# Duckuino1.net
KiCad netlist of a schematic drawn in EAGLE
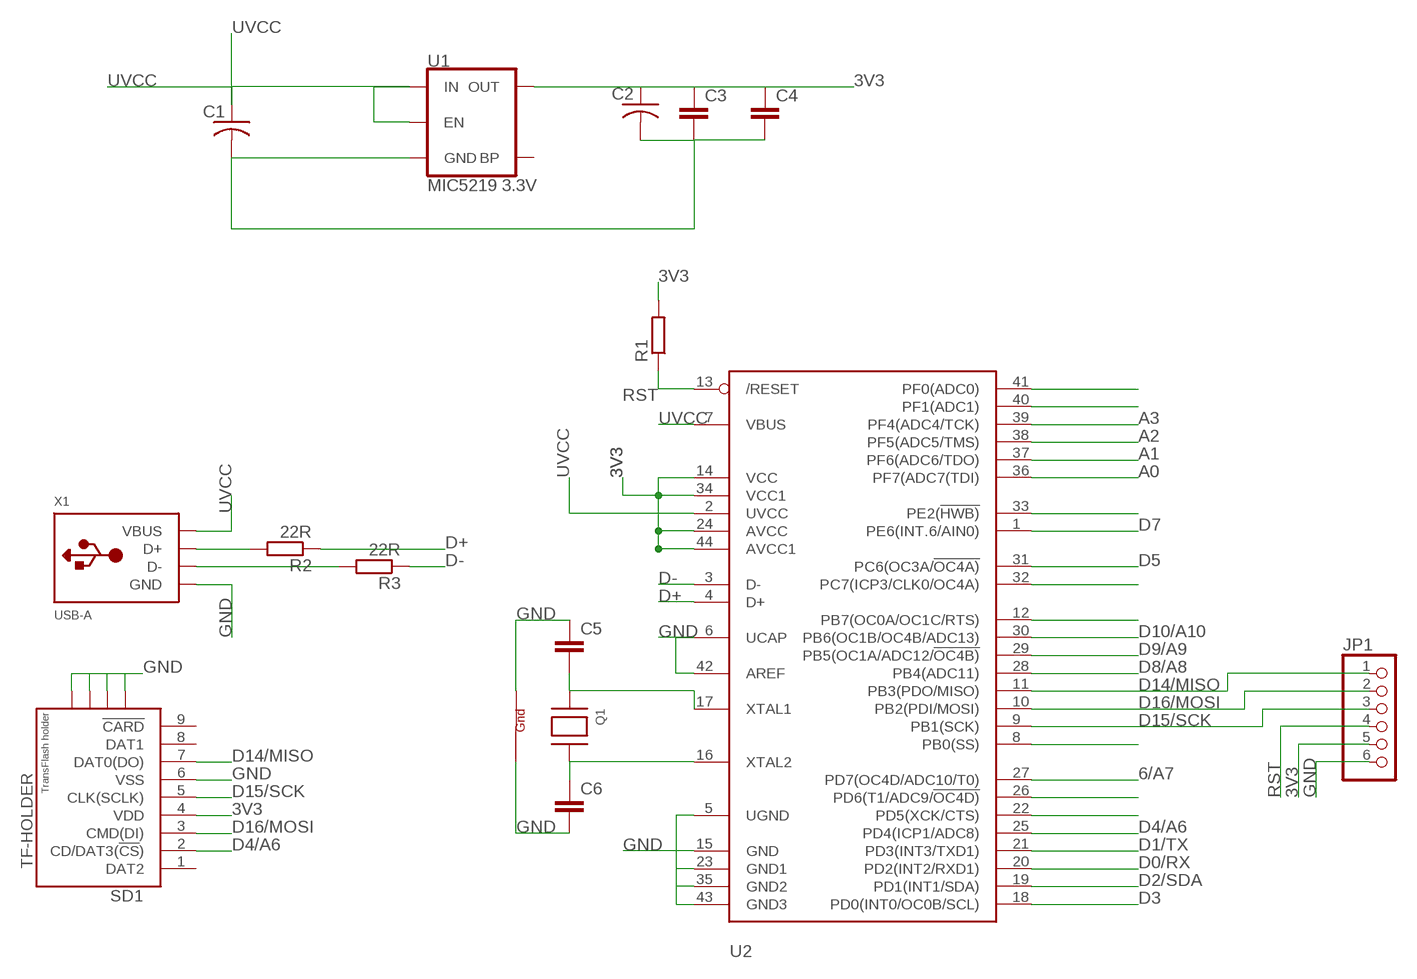
[diagram p0: schematic, sheet 1]

(export (version "E")
  (design (tool "Eeschema 10.0.6"))
  (components
    (comp (ref "C1")
      (value "C-USC0603")
      (footprint "eagle-import:C0603")
      (libsource (lib "eagle-import") (part "C-USC0603"))
    )
    (comp (ref "C2")
      (value "C-USC0603")
      (footprint "eagle-import:C0603")
      (libsource (lib "eagle-import") (part "C-USC0603"))
    )
    (comp (ref "C3")
      (value "C-EUC0603")
      (footprint "eagle-import:C0603")
      (libsource (lib "eagle-import") (part "C-EUC0603"))
    )
    (comp (ref "C4")
      (value "C-EUC0603")
      (footprint "eagle-import:C0603")
      (libsource (lib "eagle-import") (part "C-EUC0603"))
    )
    (comp (ref "C5")
      (value "C-EUC0603")
      (footprint "eagle-import:C0603")
      (libsource (lib "eagle-import") (part "C-EUC0603"))
    )
    (comp (ref "C6")
      (value "C-EUC0603")
      (footprint "eagle-import:C0603")
      (libsource (lib "eagle-import") (part "C-EUC0603"))
    )
    (comp (ref "JP1")
      (value "PINHD-1X6")
      (footprint "eagle-import:1X06")
      (libsource (lib "eagle-import") (part "PINHD-1X6"))
    )
    (comp (ref "Q1")
      (value "XTAL-4-3225")
      (footprint "eagle-import:NX3225")
      (libsource (lib "eagle-import") (part "XTAL-4-3225"))
    )
    (comp (ref "R1")
      (value "RR0603")
      (footprint "eagle-import:R0603")
      (libsource (lib "eagle-import") (part "RR0603"))
    )
    (comp (ref "R2")
      (value "22R")
      (footprint "eagle-import:R0603")
      (libsource (lib "eagle-import") (part "RR0603"))
    )
    (comp (ref "R3")
      (value "22R")
      (footprint "eagle-import:R0603")
      (libsource (lib "eagle-import") (part "RR0603"))
    )
    (comp (ref "SD1")
      (value "TF-HOLDER")
      (footprint "eagle-import:TF-PULL")
      (libsource (lib "eagle-import") (part "TF-HOLDER"))
    )
    (comp (ref "U1")
      (value "MIC5219 3.3V")
      (footprint "eagle-import:SOT23-5")
      (libsource (lib "eagle-import") (part "V_REG_MIC52193.3V"))
    )
    (comp (ref "U2")
      (value "ATMEGA32U4-AU")
      (footprint "eagle-import:TQFP44")
      (libsource (lib "eagle-import") (part "ATMEGA32U4-AU"))
    )
    (comp (ref "X1")
      (value "USB-A")
      (footprint "eagle-import:MOLEX_480371000")
      (libsource (lib "eagle-import") (part "USB-A"))
    )
  )
  (nets
    (net (code "1") (name "/3V3") (class "Default")
      (node (ref "C2") (pin "1") (pinfunction "1_1") (pintype "passive"))
      (node (ref "C3") (pin "1") (pinfunction "1_1") (pintype "passive"))
      (node (ref "C4") (pin "1") (pinfunction "1_1") (pintype "passive"))
      (node (ref "JP1") (pin "5") (pinfunction "5_5") (pintype "passive"))
      (node (ref "R1") (pin "2") (pinfunction "2_2") (pintype "passive"))
      (node (ref "SD1") (pin "4") (pinfunction "VDD_4") (pintype "power_in"))
      (node (ref "U1") (pin "5") (pinfunction "OUT_5") (pintype "passive"))
      (node (ref "U2") (pin "14") (pinfunction "VCC_14") (pintype "bidirectional"))
      (node (ref "U2") (pin "24") (pinfunction "AVCC_24") (pintype "bidirectional"))
      (node (ref "U2") (pin "34") (pinfunction "VCC1_34") (pintype "bidirectional"))
      (node (ref "U2") (pin "44") (pinfunction "AVCC1_44") (pintype "bidirectional"))
    )
    (net (code "2") (name "/6{slash}A7") (class "Default")
      (node (ref "U2") (pin "27") (pinfunction "PD7(OC4D/ADC10/T0)_27") (pintype "bidirectional"))
    )
    (net (code "3") (name "/A0") (class "Default")
      (node (ref "U2") (pin "36") (pinfunction "PF7(ADC7(TDI)_36") (pintype "bidirectional"))
    )
    (net (code "4") (name "/A1") (class "Default")
      (node (ref "U2") (pin "37") (pinfunction "PF6(ADC6/TDO)_37") (pintype "bidirectional"))
    )
    (net (code "5") (name "/A2") (class "Default")
      (node (ref "U2") (pin "38") (pinfunction "PF5(ADC5/TMS)_38") (pintype "bidirectional"))
    )
    (net (code "6") (name "/A3") (class "Default")
      (node (ref "U2") (pin "39") (pinfunction "PF4(ADC4/TCK)_39") (pintype "bidirectional"))
    )
    (net (code "7") (name "/D+") (class "Default")
      (node (ref "R2") (pin "1") (pinfunction "1_1") (pintype "passive"))
      (node (ref "U2") (pin "4") (pinfunction "D+_4") (pintype "bidirectional"))
    )
    (net (code "8") (name "/D-") (class "Default")
      (node (ref "R3") (pin "1") (pinfunction "1_1") (pintype "passive"))
      (node (ref "U2") (pin "3") (pinfunction "D-_3") (pintype "bidirectional"))
    )
    (net (code "9") (name "/D0{slash}RX") (class "Default")
      (node (ref "U2") (pin "20") (pinfunction "PD2(INT2/RXD1)_20") (pintype "bidirectional"))
    )
    (net (code "10") (name "/D1{slash}TX") (class "Default")
      (node (ref "U2") (pin "21") (pinfunction "PD3(INT3/TXD1)_21") (pintype "bidirectional"))
    )
    (net (code "11") (name "/D2{slash}SDA") (class "Default")
      (node (ref "U2") (pin "19") (pinfunction "PD1(INT1/SDA)_19") (pintype "bidirectional"))
    )
    (net (code "12") (name "/D3") (class "Default")
      (node (ref "U2") (pin "18") (pinfunction "PD0(INT0/OC0B/SCL)_18") (pintype "bidirectional"))
    )
    (net (code "13") (name "/D4{slash}A6") (class "Default")
      (node (ref "SD1") (pin "2") (pinfunction "CD/DAT3(~{CS})_2") (pintype "bidirectional"))
      (node (ref "U2") (pin "25") (pinfunction "PD4(ICP1/ADC8)_25") (pintype "bidirectional"))
    )
    (net (code "14") (name "/D5") (class "Default")
      (node (ref "U2") (pin "31") (pinfunction "PC6(OC3A/~{OC4A})_31") (pintype "bidirectional"))
    )
    (net (code "15") (name "/D7") (class "Default")
      (node (ref "U2") (pin "1") (pinfunction "PE6(INT.6/AIN0)_1") (pintype "bidirectional"))
    )
    (net (code "16") (name "/D8{slash}A8") (class "Default")
      (node (ref "U2") (pin "28") (pinfunction "PB4(ADC11)_28") (pintype "bidirectional"))
    )
    (net (code "17") (name "/D9{slash}A9") (class "Default")
      (node (ref "U2") (pin "29") (pinfunction "PB5(OC1A/ADC12/~{OC4B})_29") (pintype "bidirectional"))
    )
    (net (code "18") (name "/D10{slash}A10") (class "Default")
      (node (ref "U2") (pin "30") (pinfunction "PB6(OC1B/OC4B/ADC13)_30") (pintype "bidirectional"))
    )
    (net (code "19") (name "/D14{slash}MISO") (class "Default")
      (node (ref "JP1") (pin "1") (pinfunction "1_1") (pintype "passive"))
      (node (ref "SD1") (pin "7") (pinfunction "DAT0(DO)_7") (pintype "bidirectional"))
      (node (ref "U2") (pin "11") (pinfunction "PB3(PDO/MISO)_11") (pintype "bidirectional"))
    )
    (net (code "20") (name "/D15{slash}SCK") (class "Default")
      (node (ref "JP1") (pin "3") (pinfunction "3_3") (pintype "passive"))
      (node (ref "SD1") (pin "5") (pinfunction "CLK(SCLK)_5") (pintype "input"))
      (node (ref "U2") (pin "9") (pinfunction "PB1(SCK)_9") (pintype "bidirectional"))
    )
    (net (code "21") (name "/D16{slash}MOSI") (class "Default")
      (node (ref "JP1") (pin "2") (pinfunction "2_2") (pintype "passive"))
      (node (ref "SD1") (pin "3") (pinfunction "CMD(DI)_3") (pintype "bidirectional"))
      (node (ref "U2") (pin "10") (pinfunction "PB2(PDI/MOSI)_10") (pintype "bidirectional"))
    )
    (net (code "22") (name "/GND") (class "Default")
      (node (ref "C1") (pin "2") (pinfunction "2_2") (pintype "passive"))
      (node (ref "C2") (pin "2") (pinfunction "2_2") (pintype "passive"))
      (node (ref "C3") (pin "2") (pinfunction "2_2") (pintype "passive"))
      (node (ref "C4") (pin "2") (pinfunction "2_2") (pintype "passive"))
      (node (ref "C5") (pin "1") (pinfunction "1_1") (pintype "passive"))
      (node (ref "C6") (pin "2") (pinfunction "2_2") (pintype "passive"))
      (node (ref "JP1") (pin "6") (pinfunction "6_6") (pintype "passive"))
      (node (ref "Q1") (pin "2") (pinfunction "G2_2") (pintype "power_in"))
      (node (ref "Q1") (pin "4") (pinfunction "G1_4") (pintype "power_in"))
      (node (ref "SD1") (pin "6") (pinfunction "VSS_6") (pintype "power_in"))
      (node (ref "SD1") (pin "S1") (pinfunction "S1_S1") (pintype "passive"))
      (node (ref "SD1") (pin "S2") (pinfunction "S2_S2") (pintype "passive"))
      (node (ref "SD1") (pin "S3") (pinfunction "S3_S3") (pintype "passive"))
      (node (ref "SD1") (pin "S4") (pinfunction "S4_S4") (pintype "passive"))
      (node (ref "U1") (pin "2") (pinfunction "GND_2") (pintype "input"))
      (node (ref "U2") (pin "15") (pinfunction "GND_15") (pintype "bidirectional"))
      (node (ref "U2") (pin "23") (pinfunction "GND1_23") (pintype "bidirectional"))
      (node (ref "U2") (pin "35") (pinfunction "GND2_35") (pintype "bidirectional"))
      (node (ref "U2") (pin "42") (pinfunction "AREF_42") (pintype "bidirectional"))
      (node (ref "U2") (pin "43") (pinfunction "GND3_43") (pintype "bidirectional"))
      (node (ref "U2") (pin "5") (pinfunction "UGND_5") (pintype "bidirectional"))
      (node (ref "U2") (pin "6") (pinfunction "UCAP_6") (pintype "bidirectional"))
      (node (ref "X1") (pin "4") (pinfunction "GND_4") (pintype "power_in"))
    )
    (net (code "23") (name "/RST") (class "Default")
      (node (ref "JP1") (pin "4") (pinfunction "4_4") (pintype "passive"))
      (node (ref "R1") (pin "1") (pinfunction "1_1") (pintype "passive"))
      (node (ref "U2") (pin "13") (pinfunction "/RESET_13") (pintype "bidirectional"))
    )
    (net (code "24") (name "/UVCC") (class "Default")
      (node (ref "C1") (pin "1") (pinfunction "1_1") (pintype "passive"))
      (node (ref "U1") (pin "1") (pinfunction "IN_1") (pintype "input"))
      (node (ref "U1") (pin "3") (pinfunction "EN_3") (pintype "input"))
      (node (ref "U2") (pin "2") (pinfunction "UVCC_2") (pintype "bidirectional"))
      (node (ref "U2") (pin "7") (pinfunction "VBUS_7") (pintype "bidirectional"))
      (node (ref "X1") (pin "1") (pinfunction "VBUS_1") (pintype "power_in"))
    )
    (net (code "25") (name "Net-(Q1-X1)") (class "Default")
      (node (ref "C5") (pin "2") (pinfunction "2_2") (pintype "passive"))
      (node (ref "Q1") (pin "1") (pinfunction "X1_1") (pintype "bidirectional"))
      (node (ref "U2") (pin "17") (pinfunction "XTAL1_17") (pintype "bidirectional"))
    )
    (net (code "26") (name "Net-(Q1-X2)") (class "Default")
      (node (ref "C6") (pin "1") (pinfunction "1_1") (pintype "passive"))
      (node (ref "Q1") (pin "3") (pinfunction "X2_3") (pintype "bidirectional"))
      (node (ref "U2") (pin "16") (pinfunction "XTAL2_16") (pintype "bidirectional"))
    )
    (net (code "27") (name "Net-(X1-D+)") (class "Default")
      (node (ref "R2") (pin "2") (pinfunction "2_2") (pintype "passive"))
      (node (ref "X1") (pin "3") (pinfunction "D+_3") (pintype "bidirectional"))
    )
    (net (code "28") (name "Net-(X1-D-)") (class "Default")
      (node (ref "R3") (pin "2") (pinfunction "2_2") (pintype "passive"))
      (node (ref "X1") (pin "2") (pinfunction "D-_2") (pintype "bidirectional"))
    )
    (net (code "29") (name "unconnected-(SD1-DAT1-Pad8)") (class "Default")
      (node (ref "SD1") (pin "8") (pinfunction "DAT1_8") (pintype "bidirectional"))
    )
    (net (code "30") (name "unconnected-(SD1-DAT2-Pad1)") (class "Default")
      (node (ref "SD1") (pin "1") (pinfunction "DAT2_1") (pintype "bidirectional"))
    )
    (net (code "31") (name "unconnected-(SD1-~{CARD}-Pad9)") (class "Default")
      (node (ref "SD1") (pin "9") (pinfunction "~{CARD}_9") (pintype "passive"))
    )
    (net (code "32") (name "unconnected-(U1-BP-Pad4)") (class "Default")
      (node (ref "U1") (pin "4") (pinfunction "BP_4") (pintype "input"))
    )
    (net (code "33") (name "unconnected-(U2-PB0(SS)-Pad8)") (class "Default")
      (node (ref "U2") (pin "8") (pinfunction "PB0(SS)_8") (pintype "bidirectional"))
    )
    (net (code "34") (name "unconnected-(U2-PB7(OC0A{slash}OC1C{slash}RTS)-Pad12)") (class "Default")
      (node (ref "U2") (pin "12") (pinfunction "PB7(OC0A/OC1C/RTS)_12") (pintype "bidirectional"))
    )
    (net (code "35") (name "unconnected-(U2-PC7(ICP3{slash}CLK0{slash}OC4A)-Pad32)") (class "Default")
      (node (ref "U2") (pin "32") (pinfunction "PC7(ICP3/CLK0/OC4A)_32") (pintype "bidirectional"))
    )
    (net (code "36") (name "unconnected-(U2-PD5(XCK{slash}CTS)-Pad22)") (class "Default")
      (node (ref "U2") (pin "22") (pinfunction "PD5(XCK/CTS)_22") (pintype "bidirectional"))
    )
    (net (code "37") (name "unconnected-(U2-PD6(T1{slash}ADC9{slash}~{OC4D})-Pad26)") (class "Default")
      (node (ref "U2") (pin "26") (pinfunction "PD6(T1/ADC9/~{OC4D})_26") (pintype "bidirectional"))
    )
    (net (code "38") (name "unconnected-(U2-PE2(~{HWB})-Pad33)") (class "Default")
      (node (ref "U2") (pin "33") (pinfunction "PE2(~{HWB})_33") (pintype "bidirectional"))
    )
    (net (code "39") (name "unconnected-(U2-PF0(ADC0)-Pad41)") (class "Default")
      (node (ref "U2") (pin "41") (pinfunction "PF0(ADC0)_41") (pintype "bidirectional"))
    )
    (net (code "40") (name "unconnected-(U2-PF1(ADC1)-Pad40)") (class "Default")
      (node (ref "U2") (pin "40") (pinfunction "PF1(ADC1)_40") (pintype "bidirectional"))
    )
  )
)
